# NoiseSampleHold.net
KiCad netlist of a schematic drawn in EAGLE
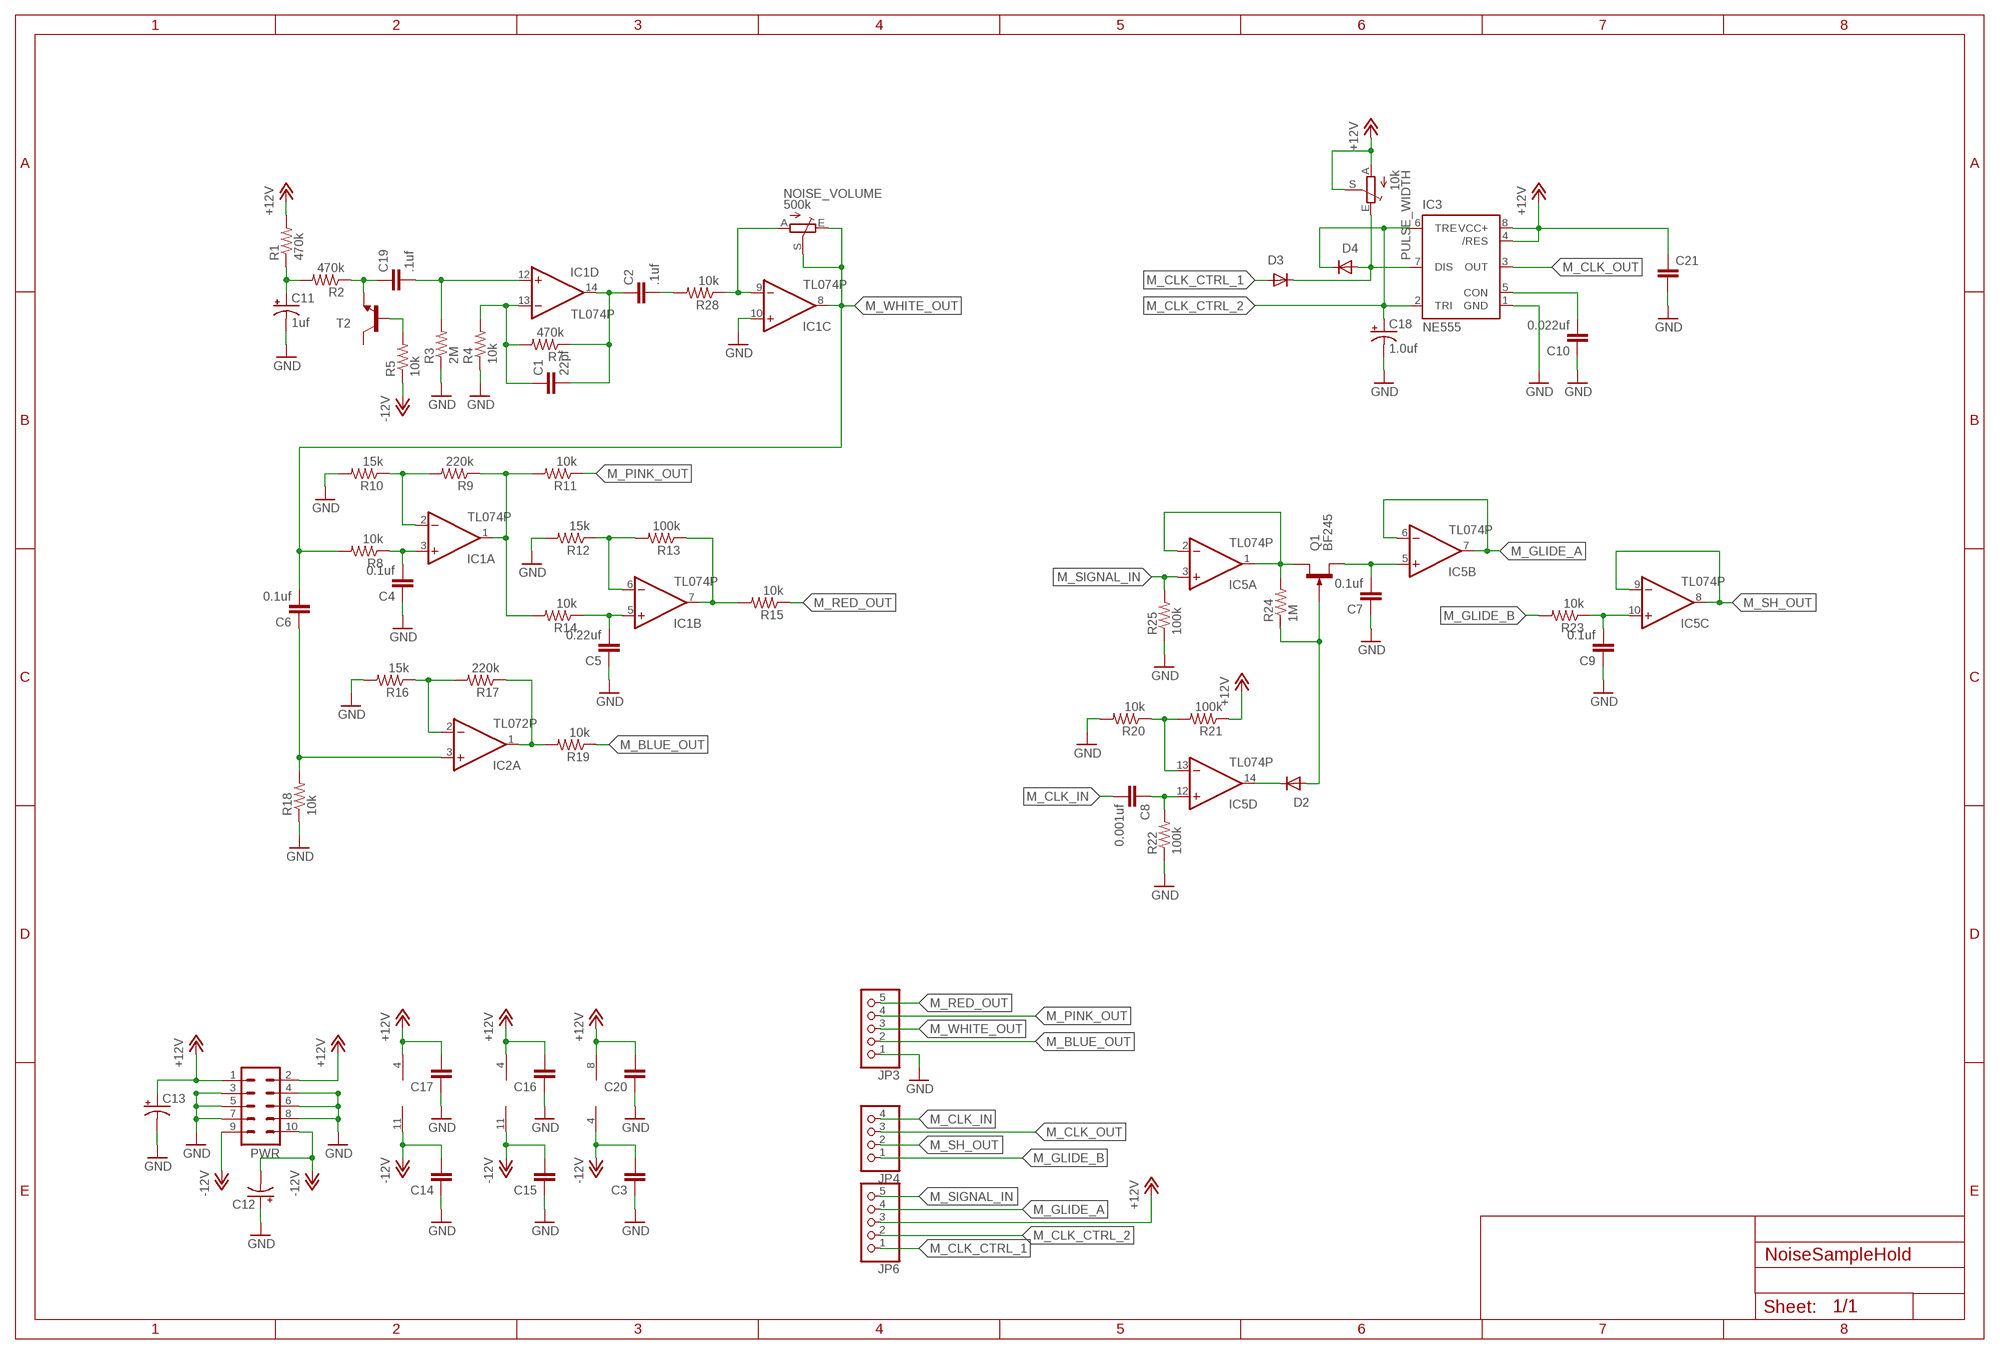
[diagram p0: schematic, sheet 1]

(export (version "E")
  (design (tool "Eeschema 10.0.6"))
  (components
    (comp (ref "C1")
      (value "22pf")
      (footprint "eagle-import:C050-024X044")
      (libsource (lib "eagle-import") (part "C-EU050-024X044"))
    )
    (comp (ref "C2")
      (value ".1uf")
      (footprint "eagle-import:C050-024X044")
      (libsource (lib "eagle-import") (part "C-EU050-024X044"))
    )
    (comp (ref "C3")
      (value "C-EU050-024X044")
      (footprint "eagle-import:C050-024X044")
      (libsource (lib "eagle-import") (part "C-EU050-024X044"))
    )
    (comp (ref "C4")
      (value "0.1uf")
      (footprint "eagle-import:C050-024X044")
      (libsource (lib "eagle-import") (part "C-EU050-024X044"))
    )
    (comp (ref "C5")
      (value "0.22uf")
      (footprint "eagle-import:C050-024X044")
      (libsource (lib "eagle-import") (part "C-EU050-024X044"))
    )
    (comp (ref "C6")
      (value "0.1uf")
      (footprint "eagle-import:C050-024X044")
      (libsource (lib "eagle-import") (part "C-EU050-024X044"))
    )
    (comp (ref "C7")
      (value "0.1uf")
      (footprint "eagle-import:C050-024X044")
      (libsource (lib "eagle-import") (part "C-EU050-024X044"))
    )
    (comp (ref "C8")
      (value "0.001uf")
      (footprint "eagle-import:C050-024X044")
      (libsource (lib "eagle-import") (part "C-EU050-024X044"))
    )
    (comp (ref "C9")
      (value "0.1uf")
      (footprint "eagle-import:C050-024X044")
      (libsource (lib "eagle-import") (part "C-EU050-024X044"))
    )
    (comp (ref "C10")
      (value "0.022uf")
      (footprint "eagle-import:C050-024X044")
      (libsource (lib "eagle-import") (part "C-EU050-024X044"))
    )
    (comp (ref "C11")
      (value "1uf")
      (footprint "eagle-import:E2,5-5")
      (libsource (lib "eagle-import") (part "CPOL-USE2.5-5"))
    )
    (comp (ref "C12")
      (value "CPOL-USE2.5-5")
      (footprint "eagle-import:E2,5-5")
      (libsource (lib "eagle-import") (part "CPOL-USE2.5-5"))
    )
    (comp (ref "C13")
      (value "CPOL-USE2.5-5")
      (footprint "eagle-import:E2,5-5")
      (libsource (lib "eagle-import") (part "CPOL-USE2.5-5"))
    )
    (comp (ref "C14")
      (value "C-EU050-024X044")
      (footprint "eagle-import:C050-024X044")
      (libsource (lib "eagle-import") (part "C-EU050-024X044"))
    )
    (comp (ref "C15")
      (value "C-EU050-024X044")
      (footprint "eagle-import:C050-024X044")
      (libsource (lib "eagle-import") (part "C-EU050-024X044"))
    )
    (comp (ref "C16")
      (value "C-EU050-024X044")
      (footprint "eagle-import:C050-024X044")
      (libsource (lib "eagle-import") (part "C-EU050-024X044"))
    )
    (comp (ref "C17")
      (value "C-EU050-024X044")
      (footprint "eagle-import:C050-024X044")
      (libsource (lib "eagle-import") (part "C-EU050-024X044"))
    )
    (comp (ref "C18")
      (value "1.0uf")
      (footprint "eagle-import:E2,5-5")
      (libsource (lib "eagle-import") (part "CPOL-USE2.5-5"))
    )
    (comp (ref "C19")
      (value ".1uf")
      (footprint "eagle-import:C050-024X044")
      (libsource (lib "eagle-import") (part "C-EU050-024X044"))
    )
    (comp (ref "C20")
      (value "C-EU050-024X044")
      (footprint "eagle-import:C050-024X044")
      (libsource (lib "eagle-import") (part "C-EU050-024X044"))
    )
    (comp (ref "C21")
      (value "C-EU050-024X044")
      (footprint "eagle-import:C050-024X044")
      (libsource (lib "eagle-import") (part "C-EU050-024X044"))
    )
    (comp (ref "D2")
      (value "1N4148DO35-7")
      (footprint "eagle-import:DO35-7")
      (libsource (lib "eagle-import") (part "1N4148DO35-7"))
    )
    (comp (ref "D3")
      (value "1N4148DO35-7")
      (footprint "eagle-import:DO35-7")
      (libsource (lib "eagle-import") (part "1N4148DO35-7"))
    )
    (comp (ref "D4")
      (value "1N4148DO35-7")
      (footprint "eagle-import:DO35-7")
      (libsource (lib "eagle-import") (part "1N4148DO35-7"))
    )
    (comp (ref "IC1")
      (value "TL074P")
      (footprint "eagle-import:DIL14")
      (libsource (lib "eagle-import") (part "TL074P"))
    )
    (comp (ref "IC2")
      (value "TL072P")
      (footprint "eagle-import:DIL08")
      (libsource (lib "eagle-import") (part "TL072P"))
    )
    (comp (ref "IC3")
      (value "NE555")
      (footprint "eagle-import:DIL-08")
      (fields (field (name "MF") "Arrow Electronics") (field (name "MPN") "NE555N"))
      (libsource (lib "eagle-import") (part "NE555"))
    )
    (comp (ref "IC5")
      (value "TL074P")
      (footprint "eagle-import:DIL14")
      (libsource (lib "eagle-import") (part "TL074P"))
    )
    (comp (ref "JP3")
      (value "PINHD-1X5")
      (footprint "eagle-import:1X05")
      (libsource (lib "eagle-import") (part "PINHD-1X5"))
    )
    (comp (ref "JP4")
      (value "PINHD-1X4")
      (footprint "eagle-import:1X04")
      (libsource (lib "eagle-import") (part "PINHD-1X4"))
    )
    (comp (ref "JP6")
      (value "PINHD-1X5")
      (footprint "eagle-import:1X05")
      (libsource (lib "eagle-import") (part "PINHD-1X5"))
    )
    (comp (ref "NOISE_VOLUME")
      (value "500k")
      (footprint "eagle-import:S64YW")
      (libsource (lib "eagle-import") (part "TRIM_1234-S64YW"))
    )
    (comp (ref "PULSE_WIDTH")
      (value "10k")
      (footprint "eagle-import:S64YW")
      (libsource (lib "eagle-import") (part "TRIM_1234-S64YW"))
    )
    (comp (ref "PWR")
      (value "ML10")
      (footprint "eagle-import:ML10")
      (libsource (lib "eagle-import") (part "ML10"))
    )
    (comp (ref "Q1")
      (value "BF245")
      (footprint "eagle-import:SOT54C")
      (libsource (lib "eagle-import") (part "BF245"))
    )
    (comp (ref "R1")
      (value "470k")
      (footprint "eagle-import:0204_7")
      (libsource (lib "eagle-import") (part "R-US_0204/7"))
    )
    (comp (ref "R2")
      (value "470k")
      (footprint "eagle-import:0204_7")
      (libsource (lib "eagle-import") (part "R-US_0204/7"))
    )
    (comp (ref "R3")
      (value "2M")
      (footprint "eagle-import:0204_7")
      (libsource (lib "eagle-import") (part "R-US_0204/7"))
    )
    (comp (ref "R4")
      (value "10k")
      (footprint "eagle-import:0204_7")
      (libsource (lib "eagle-import") (part "R-US_0204/7"))
    )
    (comp (ref "R5")
      (value "10k")
      (footprint "eagle-import:0204_7")
      (libsource (lib "eagle-import") (part "R-US_0204/7"))
    )
    (comp (ref "R7")
      (value "470k")
      (footprint "eagle-import:0204_7")
      (libsource (lib "eagle-import") (part "R-US_0204/7"))
    )
    (comp (ref "R8")
      (value "10k")
      (footprint "eagle-import:0204_7")
      (libsource (lib "eagle-import") (part "R-US_0204/7"))
    )
    (comp (ref "R9")
      (value "220k")
      (footprint "eagle-import:0204_7")
      (libsource (lib "eagle-import") (part "R-US_0204/7"))
    )
    (comp (ref "R10")
      (value "15k")
      (footprint "eagle-import:0204_7")
      (libsource (lib "eagle-import") (part "R-US_0204/7"))
    )
    (comp (ref "R11")
      (value "10k")
      (footprint "eagle-import:0204_7")
      (libsource (lib "eagle-import") (part "R-US_0204/7"))
    )
    (comp (ref "R12")
      (value "15k")
      (footprint "eagle-import:0204_7")
      (libsource (lib "eagle-import") (part "R-US_0204/7"))
    )
    (comp (ref "R13")
      (value "100k")
      (footprint "eagle-import:0204_7")
      (libsource (lib "eagle-import") (part "R-US_0204/7"))
    )
    (comp (ref "R14")
      (value "10k")
      (footprint "eagle-import:0204_7")
      (libsource (lib "eagle-import") (part "R-US_0204/7"))
    )
    (comp (ref "R15")
      (value "10k")
      (footprint "eagle-import:0204_7")
      (libsource (lib "eagle-import") (part "R-US_0204/7"))
    )
    (comp (ref "R16")
      (value "15k")
      (footprint "eagle-import:0204_7")
      (libsource (lib "eagle-import") (part "R-US_0204/7"))
    )
    (comp (ref "R17")
      (value "220k")
      (footprint "eagle-import:0204_7")
      (libsource (lib "eagle-import") (part "R-US_0204/7"))
    )
    (comp (ref "R18")
      (value "10k")
      (footprint "eagle-import:0204_7")
      (libsource (lib "eagle-import") (part "R-US_0204/7"))
    )
    (comp (ref "R19")
      (value "10k")
      (footprint "eagle-import:0204_7")
      (libsource (lib "eagle-import") (part "R-US_0204/7"))
    )
    (comp (ref "R20")
      (value "10k")
      (footprint "eagle-import:0204_7")
      (libsource (lib "eagle-import") (part "R-US_0204/7"))
    )
    (comp (ref "R21")
      (value "100k")
      (footprint "eagle-import:0204_7")
      (libsource (lib "eagle-import") (part "R-US_0204/7"))
    )
    (comp (ref "R22")
      (value "100k")
      (footprint "eagle-import:0204_7")
      (libsource (lib "eagle-import") (part "R-US_0204/7"))
    )
    (comp (ref "R23")
      (value "10k")
      (footprint "eagle-import:0204_7")
      (libsource (lib "eagle-import") (part "R-US_0204/7"))
    )
    (comp (ref "R24")
      (value "1M")
      (footprint "eagle-import:0204_7")
      (libsource (lib "eagle-import") (part "R-US_0204/7"))
    )
    (comp (ref "R25")
      (value "100k")
      (footprint "eagle-import:0204_7")
      (libsource (lib "eagle-import") (part "R-US_0204/7"))
    )
    (comp (ref "R28")
      (value "10k")
      (footprint "eagle-import:0204_7")
      (libsource (lib "eagle-import") (part "R-US_0204/7"))
    )
    (comp (ref "T2")
      (value "2N3904-NPN-TO92-EBC")
      (footprint "eagle-import:TO92-EBC")
      (libsource (lib "eagle-import") (part "-NPN-TO92-EBC2N3904"))
    )
  )
  (nets
    (net (code "1") (name "+12V") (class "Default")
      (node (ref "C13") (pin "+") (pinfunction "+_+") (pintype "passive"))
      (node (ref "C16") (pin "2") (pinfunction "2_2") (pintype "passive"))
      (node (ref "C17") (pin "2") (pinfunction "2_2") (pintype "passive"))
      (node (ref "C20") (pin "2") (pinfunction "2_2") (pintype "passive"))
      (node (ref "C21") (pin "1") (pinfunction "1_1") (pintype "passive"))
      (node (ref "IC1") (pin "4") (pinfunction "V+_4") (pintype "power_in"))
      (node (ref "IC2") (pin "8") (pinfunction "V+_8") (pintype "power_in"))
      (node (ref "IC3") (pin "4") (pinfunction "/RES_4") (pintype "input"))
      (node (ref "IC3") (pin "8") (pinfunction "VCC+_8") (pintype "power_in"))
      (node (ref "IC5") (pin "4") (pinfunction "V+_4") (pintype "power_in"))
      (node (ref "JP6") (pin "3") (pinfunction "3_3") (pintype "passive"))
      (node (ref "PULSE_WIDTH") (pin "A") (pinfunction "A_A") (pintype "passive"))
      (node (ref "PULSE_WIDTH") (pin "S") (pinfunction "S_S") (pintype "passive"))
      (node (ref "PWR") (pin "1") (pinfunction "1_1") (pintype "passive"))
      (node (ref "PWR") (pin "2") (pinfunction "2_2") (pintype "passive"))
      (node (ref "R1") (pin "2") (pinfunction "2_2") (pintype "passive"))
      (node (ref "R21") (pin "1") (pinfunction "1_1") (pintype "passive"))
    )
    (net (code "2") (name "-12V") (class "Default")
      (node (ref "C12") (pin "-") (pinfunction "-_-") (pintype "passive"))
      (node (ref "C14") (pin "2") (pinfunction "2_2") (pintype "passive"))
      (node (ref "C15") (pin "2") (pinfunction "2_2") (pintype "passive"))
      (node (ref "C3") (pin "2") (pinfunction "2_2") (pintype "passive"))
      (node (ref "IC1") (pin "11") (pinfunction "V-_11") (pintype "power_in"))
      (node (ref "IC2") (pin "4") (pinfunction "V-_4") (pintype "power_in"))
      (node (ref "IC5") (pin "11") (pinfunction "V-_11") (pintype "power_in"))
      (node (ref "PWR") (pin "10") (pinfunction "10_10") (pintype "passive"))
      (node (ref "PWR") (pin "9") (pinfunction "9_9") (pintype "passive"))
      (node (ref "R5") (pin "1") (pinfunction "1_1") (pintype "passive"))
    )
    (net (code "3") (name "GND") (class "Default")
      (node (ref "C10") (pin "1") (pinfunction "1_1") (pintype "passive"))
      (node (ref "C11") (pin "-") (pinfunction "-_-") (pintype "passive"))
      (node (ref "C12") (pin "+") (pinfunction "+_+") (pintype "passive"))
      (node (ref "C13") (pin "-") (pinfunction "-_-") (pintype "passive"))
      (node (ref "C14") (pin "1") (pinfunction "1_1") (pintype "passive"))
      (node (ref "C15") (pin "1") (pinfunction "1_1") (pintype "passive"))
      (node (ref "C16") (pin "1") (pinfunction "1_1") (pintype "passive"))
      (node (ref "C17") (pin "1") (pinfunction "1_1") (pintype "passive"))
      (node (ref "C18") (pin "-") (pinfunction "-_-") (pintype "passive"))
      (node (ref "C20") (pin "1") (pinfunction "1_1") (pintype "passive"))
      (node (ref "C21") (pin "2") (pinfunction "2_2") (pintype "passive"))
      (node (ref "C3") (pin "1") (pinfunction "1_1") (pintype "passive"))
      (node (ref "C4") (pin "1") (pinfunction "1_1") (pintype "passive"))
      (node (ref "C5") (pin "1") (pinfunction "1_1") (pintype "passive"))
      (node (ref "C7") (pin "1") (pinfunction "1_1") (pintype "passive"))
      (node (ref "C9") (pin "1") (pinfunction "1_1") (pintype "passive"))
      (node (ref "IC1") (pin "10") (pinfunction "+IN_10") (pintype "input"))
      (node (ref "IC3") (pin "1") (pinfunction "GND_1") (pintype "power_in"))
      (node (ref "JP3") (pin "1") (pinfunction "1_1") (pintype "passive"))
      (node (ref "PWR") (pin "3") (pinfunction "3_3") (pintype "passive"))
      (node (ref "PWR") (pin "4") (pinfunction "4_4") (pintype "passive"))
      (node (ref "PWR") (pin "5") (pinfunction "5_5") (pintype "passive"))
      (node (ref "PWR") (pin "6") (pinfunction "6_6") (pintype "passive"))
      (node (ref "PWR") (pin "7") (pinfunction "7_7") (pintype "passive"))
      (node (ref "PWR") (pin "8") (pinfunction "8_8") (pintype "passive"))
      (node (ref "R10") (pin "2") (pinfunction "2_2") (pintype "passive"))
      (node (ref "R12") (pin "2") (pinfunction "2_2") (pintype "passive"))
      (node (ref "R16") (pin "2") (pinfunction "2_2") (pintype "passive"))
      (node (ref "R18") (pin "1") (pinfunction "1_1") (pintype "passive"))
      (node (ref "R20") (pin "2") (pinfunction "2_2") (pintype "passive"))
      (node (ref "R22") (pin "1") (pinfunction "1_1") (pintype "passive"))
      (node (ref "R25") (pin "1") (pinfunction "1_1") (pintype "passive"))
      (node (ref "R3") (pin "1") (pinfunction "1_1") (pintype "passive"))
      (node (ref "R4") (pin "1") (pinfunction "1_1") (pintype "passive"))
    )
    (net (code "4") (name "M_BLUE_OUT") (class "Default")
      (node (ref "JP3") (pin "2") (pinfunction "2_2") (pintype "passive"))
      (node (ref "R19") (pin "1") (pinfunction "1_1") (pintype "passive"))
    )
    (net (code "5") (name "M_CLK_CTRL_1") (class "Default")
      (node (ref "D3") (pin "A") (pinfunction "A_A") (pintype "passive"))
      (node (ref "JP6") (pin "1") (pinfunction "1_1") (pintype "passive"))
    )
    (net (code "6") (name "M_CLK_CTRL_2") (class "Default")
      (node (ref "C18") (pin "+") (pinfunction "+_+") (pintype "passive"))
      (node (ref "D4") (pin "C") (pinfunction "C_C") (pintype "passive"))
      (node (ref "IC3") (pin "2") (pinfunction "TRI_2") (pintype "input"))
      (node (ref "IC3") (pin "6") (pinfunction "TRE_6") (pintype "input"))
      (node (ref "JP6") (pin "2") (pinfunction "2_2") (pintype "passive"))
    )
    (net (code "7") (name "M_CLK_IN") (class "Default")
      (node (ref "C8") (pin "2") (pinfunction "2_2") (pintype "passive"))
      (node (ref "JP4") (pin "4") (pinfunction "4_4") (pintype "passive"))
    )
    (net (code "8") (name "M_CLK_OUT") (class "Default")
      (node (ref "IC3") (pin "3") (pinfunction "OUT_3") (pintype "output"))
      (node (ref "JP4") (pin "3") (pinfunction "3_3") (pintype "passive"))
    )
    (net (code "9") (name "M_GLIDE_A") (class "Default")
      (node (ref "IC5") (pin "6") (pinfunction "-IN_6") (pintype "input"))
      (node (ref "IC5") (pin "7") (pinfunction "OUT_7") (pintype "output"))
      (node (ref "JP6") (pin "4") (pinfunction "4_4") (pintype "passive"))
    )
    (net (code "10") (name "M_GLIDE_B") (class "Default")
      (node (ref "JP4") (pin "1") (pinfunction "1_1") (pintype "passive"))
      (node (ref "R23") (pin "2") (pinfunction "2_2") (pintype "passive"))
    )
    (net (code "11") (name "M_PINK_OUT") (class "Default")
      (node (ref "JP3") (pin "4") (pinfunction "4_4") (pintype "passive"))
      (node (ref "R11") (pin "1") (pinfunction "1_1") (pintype "passive"))
    )
    (net (code "12") (name "M_RED_OUT") (class "Default")
      (node (ref "JP3") (pin "5") (pinfunction "5_5") (pintype "passive"))
      (node (ref "R15") (pin "1") (pinfunction "1_1") (pintype "passive"))
    )
    (net (code "13") (name "M_SH_OUT") (class "Default")
      (node (ref "IC5") (pin "8") (pinfunction "OUT_8") (pintype "output"))
      (node (ref "IC5") (pin "9") (pinfunction "-IN_9") (pintype "input"))
      (node (ref "JP4") (pin "2") (pinfunction "2_2") (pintype "passive"))
    )
    (net (code "14") (name "M_SIGNAL_IN") (class "Default")
      (node (ref "IC5") (pin "3") (pinfunction "+IN_3") (pintype "input"))
      (node (ref "JP6") (pin "5") (pinfunction "5_5") (pintype "passive"))
      (node (ref "R25") (pin "2") (pinfunction "2_2") (pintype "passive"))
    )
    (net (code "15") (name "M_WHITE_OUT") (class "Default")
      (node (ref "C6") (pin "2") (pinfunction "2_2") (pintype "passive"))
      (node (ref "IC1") (pin "8") (pinfunction "OUT_8") (pintype "output"))
      (node (ref "JP3") (pin "3") (pinfunction "3_3") (pintype "passive"))
      (node (ref "NOISE_VOLUME") (pin "E") (pinfunction "E_E") (pintype "passive"))
      (node (ref "NOISE_VOLUME") (pin "S") (pinfunction "S_S") (pintype "passive"))
      (node (ref "R8") (pin "2") (pinfunction "2_2") (pintype "passive"))
    )
    (net (code "16") (name "Net-(C2-Pad2)") (class "Default")
      (node (ref "C2") (pin "2") (pinfunction "2_2") (pintype "passive"))
      (node (ref "R28") (pin "2") (pinfunction "2_2") (pintype "passive"))
    )
    (net (code "17") (name "Net-(C11-Pad+)") (class "Default")
      (node (ref "C11") (pin "+") (pinfunction "+_+") (pintype "passive"))
      (node (ref "R1") (pin "1") (pinfunction "1_1") (pintype "passive"))
      (node (ref "R2") (pin "2") (pinfunction "2_2") (pintype "passive"))
    )
    (net (code "18") (name "Net-(C19-Pad1)") (class "Default")
      (node (ref "C19") (pin "1") (pinfunction "1_1") (pintype "passive"))
      (node (ref "R2") (pin "1") (pinfunction "1_1") (pintype "passive"))
      (node (ref "T2") (pin "E") (pinfunction "E_E") (pintype "passive"))
    )
    (net (code "19") (name "Net-(D2-PadA)") (class "Default")
      (node (ref "D2") (pin "A") (pinfunction "A_A") (pintype "passive"))
      (node (ref "Q1") (pin "G") (pinfunction "G_G") (pintype "passive"))
      (node (ref "R24") (pin "1") (pinfunction "1_1") (pintype "passive"))
    )
    (net (code "20") (name "Net-(IC1A-+IN)") (class "Default")
      (node (ref "C4") (pin "2") (pinfunction "2_2") (pintype "passive"))
      (node (ref "IC1") (pin "3") (pinfunction "+IN_3") (pintype "input"))
      (node (ref "R8") (pin "1") (pinfunction "1_1") (pintype "passive"))
    )
    (net (code "21") (name "Net-(IC1A--IN)") (class "Default")
      (node (ref "IC1") (pin "2") (pinfunction "-IN_2") (pintype "input"))
      (node (ref "R10") (pin "1") (pinfunction "1_1") (pintype "passive"))
      (node (ref "R9") (pin "2") (pinfunction "2_2") (pintype "passive"))
    )
    (net (code "22") (name "Net-(IC1A-OUT)") (class "Default")
      (node (ref "IC1") (pin "1") (pinfunction "OUT_1") (pintype "output"))
      (node (ref "R11") (pin "2") (pinfunction "2_2") (pintype "passive"))
      (node (ref "R14") (pin "2") (pinfunction "2_2") (pintype "passive"))
      (node (ref "R9") (pin "1") (pinfunction "1_1") (pintype "passive"))
    )
    (net (code "23") (name "Net-(IC1B-+IN)") (class "Default")
      (node (ref "C5") (pin "2") (pinfunction "2_2") (pintype "passive"))
      (node (ref "IC1") (pin "5") (pinfunction "+IN_5") (pintype "input"))
      (node (ref "R14") (pin "1") (pinfunction "1_1") (pintype "passive"))
    )
    (net (code "24") (name "Net-(IC1B--IN)") (class "Default")
      (node (ref "IC1") (pin "6") (pinfunction "-IN_6") (pintype "input"))
      (node (ref "R12") (pin "1") (pinfunction "1_1") (pintype "passive"))
      (node (ref "R13") (pin "2") (pinfunction "2_2") (pintype "passive"))
    )
    (net (code "25") (name "Net-(IC1B-OUT)") (class "Default")
      (node (ref "IC1") (pin "7") (pinfunction "OUT_7") (pintype "output"))
      (node (ref "R13") (pin "1") (pinfunction "1_1") (pintype "passive"))
      (node (ref "R15") (pin "2") (pinfunction "2_2") (pintype "passive"))
    )
    (net (code "26") (name "Net-(IC1C--IN)") (class "Default")
      (node (ref "IC1") (pin "9") (pinfunction "-IN_9") (pintype "input"))
      (node (ref "NOISE_VOLUME") (pin "A") (pinfunction "A_A") (pintype "passive"))
      (node (ref "R28") (pin "1") (pinfunction "1_1") (pintype "passive"))
    )
    (net (code "27") (name "Net-(IC1D-+IN)") (class "Default")
      (node (ref "C19") (pin "2") (pinfunction "2_2") (pintype "passive"))
      (node (ref "IC1") (pin "12") (pinfunction "+IN_12") (pintype "input"))
      (node (ref "R3") (pin "2") (pinfunction "2_2") (pintype "passive"))
    )
    (net (code "28") (name "Net-(IC1D--IN)") (class "Default")
      (node (ref "C1") (pin "1") (pinfunction "1_1") (pintype "passive"))
      (node (ref "IC1") (pin "13") (pinfunction "-IN_13") (pintype "input"))
      (node (ref "R4") (pin "2") (pinfunction "2_2") (pintype "passive"))
      (node (ref "R7") (pin "2") (pinfunction "2_2") (pintype "passive"))
    )
    (net (code "29") (name "Net-(IC1D-OUT)") (class "Default")
      (node (ref "C1") (pin "2") (pinfunction "2_2") (pintype "passive"))
      (node (ref "C2") (pin "1") (pinfunction "1_1") (pintype "passive"))
      (node (ref "IC1") (pin "14") (pinfunction "OUT_14") (pintype "output"))
      (node (ref "R7") (pin "1") (pinfunction "1_1") (pintype "passive"))
    )
    (net (code "30") (name "Net-(IC2A-+IN)") (class "Default")
      (node (ref "C6") (pin "1") (pinfunction "1_1") (pintype "passive"))
      (node (ref "IC2") (pin "3") (pinfunction "+IN_3") (pintype "input"))
      (node (ref "R18") (pin "2") (pinfunction "2_2") (pintype "passive"))
    )
    (net (code "31") (name "Net-(IC2A--IN)") (class "Default")
      (node (ref "IC2") (pin "2") (pinfunction "-IN_2") (pintype "input"))
      (node (ref "R16") (pin "1") (pinfunction "1_1") (pintype "passive"))
      (node (ref "R17") (pin "2") (pinfunction "2_2") (pintype "passive"))
    )
    (net (code "32") (name "Net-(IC2A-OUT)") (class "Default")
      (node (ref "IC2") (pin "1") (pinfunction "OUT_1") (pintype "output"))
      (node (ref "R17") (pin "1") (pinfunction "1_1") (pintype "passive"))
      (node (ref "R19") (pin "2") (pinfunction "2_2") (pintype "passive"))
    )
    (net (code "33") (name "Net-(IC3-CON)") (class "Default")
      (node (ref "C10") (pin "2") (pinfunction "2_2") (pintype "passive"))
      (node (ref "IC3") (pin "5") (pinfunction "CON_5") (pintype "input"))
    )
    (net (code "34") (name "Net-(IC3-DIS)") (class "Default")
      (node (ref "D3") (pin "C") (pinfunction "C_C") (pintype "passive"))
      (node (ref "D4") (pin "A") (pinfunction "A_A") (pintype "passive"))
      (node (ref "IC3") (pin "7") (pinfunction "DIS_7") (pintype "input"))
      (node (ref "PULSE_WIDTH") (pin "E") (pinfunction "E_E") (pintype "passive"))
    )
    (net (code "35") (name "Net-(IC5A--IN)") (class "Default")
      (node (ref "IC5") (pin "1") (pinfunction "OUT_1") (pintype "output"))
      (node (ref "IC5") (pin "2") (pinfunction "-IN_2") (pintype "input"))
      (node (ref "Q1") (pin "D") (pinfunction "D_D") (pintype "passive"))
      (node (ref "R24") (pin "2") (pinfunction "2_2") (pintype "passive"))
    )
    (net (code "36") (name "Net-(IC5B-+IN)") (class "Default")
      (node (ref "C7") (pin "2") (pinfunction "2_2") (pintype "passive"))
      (node (ref "IC5") (pin "5") (pinfunction "+IN_5") (pintype "input"))
      (node (ref "Q1") (pin "S") (pinfunction "S_S") (pintype "passive"))
    )
    (net (code "37") (name "Net-(IC5C-+IN)") (class "Default")
      (node (ref "C9") (pin "2") (pinfunction "2_2") (pintype "passive"))
      (node (ref "IC5") (pin "10") (pinfunction "+IN_10") (pintype "input"))
      (node (ref "R23") (pin "1") (pinfunction "1_1") (pintype "passive"))
    )
    (net (code "38") (name "Net-(IC5D-+IN)") (class "Default")
      (node (ref "C8") (pin "1") (pinfunction "1_1") (pintype "passive"))
      (node (ref "IC5") (pin "12") (pinfunction "+IN_12") (pintype "input"))
      (node (ref "R22") (pin "2") (pinfunction "2_2") (pintype "passive"))
    )
    (net (code "39") (name "Net-(IC5D--IN)") (class "Default")
      (node (ref "IC5") (pin "13") (pinfunction "-IN_13") (pintype "input"))
      (node (ref "R20") (pin "1") (pinfunction "1_1") (pintype "passive"))
      (node (ref "R21") (pin "2") (pinfunction "2_2") (pintype "passive"))
    )
    (net (code "40") (name "Net-(IC5D-OUT)") (class "Default")
      (node (ref "D2") (pin "C") (pinfunction "C_C") (pintype "passive"))
      (node (ref "IC5") (pin "14") (pinfunction "OUT_14") (pintype "output"))
    )
    (net (code "41") (name "Net-(R5-Pad2)") (class "Default")
      (node (ref "R5") (pin "2") (pinfunction "2_2") (pintype "passive"))
      (node (ref "T2") (pin "B") (pinfunction "B_B") (pintype "passive"))
    )
    (net (code "42") (name "unconnected-(NOISE_VOLUME-S-PadS@1)") (class "Default")
      (node (ref "NOISE_VOLUME") (pin "S@1") (pinfunction "S_S@1") (pintype "passive"))
    )
    (net (code "43") (name "unconnected-(PULSE_WIDTH-S-PadS@1)") (class "Default")
      (node (ref "PULSE_WIDTH") (pin "S@1") (pinfunction "S_S@1") (pintype "passive"))
    )
    (net (code "44") (name "unconnected-(T2-PadC)") (class "Default")
      (node (ref "T2") (pin "C") (pinfunction "C_C") (pintype "passive"))
    )
  )
)
